# rf.net
KiCad netlist of a schematic drawn in Altium Designer
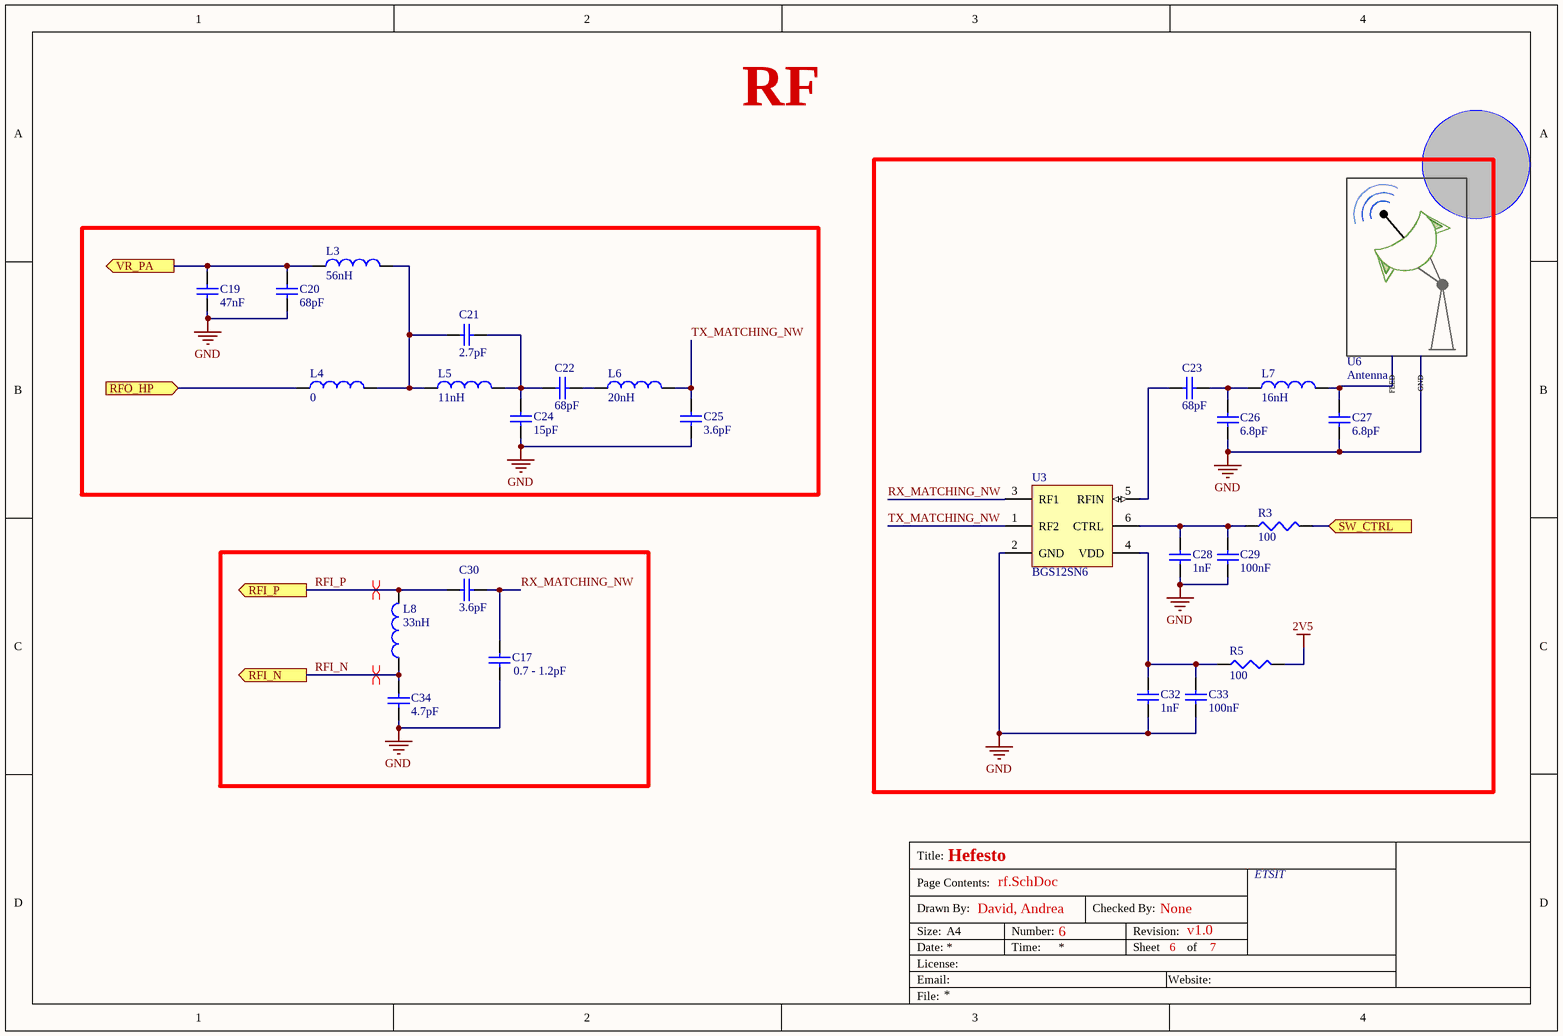
[diagram p0: rf.SchDoc]

(export (version "E")
  (design (tool "Eeschema 10.0.6"))
  (components
    (comp (ref "C17")
      (value "0.7 - 1.2pF")
      (footprint "1608[0603]")
      (description "Capacitor (Semiconductor SIM Model)")
      (fields (field (name "Comment") "Cap Semi") (field (name "PUBLISHER") "Altium Limited"))
      (libsource (lib "Miscellaneous Devices") (part "Cap Semi"))
    )
    (comp (ref "C19")
      (value "47nF")
      (footprint "1608[0603]")
      (description "Capacitor (Semiconductor SIM Model)")
      (fields (field (name "Comment") "Cap Semi") (field (name "PUBLISHER") "Altium Limited"))
      (libsource (lib "Miscellaneous Devices") (part "Cap Semi"))
    )
    (comp (ref "C20")
      (value "68pF")
      (footprint "1608[0603]")
      (description "Capacitor (Semiconductor SIM Model)")
      (fields (field (name "Comment") "Cap Semi") (field (name "PUBLISHER") "Altium Limited"))
      (libsource (lib "Miscellaneous Devices") (part "Cap Semi"))
    )
    (comp (ref "C21")
      (value "2.7pF")
      (footprint "1608[0603]")
      (description "Capacitor (Semiconductor SIM Model)")
      (fields (field (name "Comment") "Cap Semi") (field (name "PUBLISHER") "Altium Limited"))
      (libsource (lib "Miscellaneous Devices") (part "Cap Semi"))
    )
    (comp (ref "C22")
      (value "68pF")
      (footprint "1608[0603]")
      (description "Capacitor (Semiconductor SIM Model)")
      (fields (field (name "Comment") "Cap Semi") (field (name "PUBLISHER") "Altium Limited"))
      (libsource (lib "Miscellaneous Devices") (part "Cap Semi"))
    )
    (comp (ref "C23")
      (value "68pF")
      (footprint "1608[0603]")
      (description "Capacitor (Semiconductor SIM Model)")
      (fields (field (name "Comment") "Cap Semi") (field (name "PUBLISHER") "Altium Limited"))
      (libsource (lib "Miscellaneous Devices") (part "Cap Semi"))
    )
    (comp (ref "C24")
      (value "15pF")
      (footprint "1608[0603]")
      (description "Capacitor (Semiconductor SIM Model)")
      (fields (field (name "Comment") "Cap Semi") (field (name "PUBLISHER") "Altium Limited"))
      (libsource (lib "Miscellaneous Devices") (part "Cap Semi"))
    )
    (comp (ref "C25")
      (value "3.6pF")
      (footprint "1608[0603]")
      (description "Capacitor (Semiconductor SIM Model)")
      (fields (field (name "Comment") "Cap Semi") (field (name "PUBLISHER") "Altium Limited"))
      (libsource (lib "Miscellaneous Devices") (part "Cap Semi"))
    )
    (comp (ref "C26")
      (value "6.8pF")
      (footprint "1608[0603]")
      (description "Capacitor (Semiconductor SIM Model)")
      (fields (field (name "Comment") "Cap Semi") (field (name "PUBLISHER") "Altium Limited"))
      (libsource (lib "Miscellaneous Devices") (part "Cap Semi"))
    )
    (comp (ref "C27")
      (value "6.8pF")
      (footprint "1608[0603]")
      (description "Capacitor (Semiconductor SIM Model)")
      (fields (field (name "Comment") "Cap Semi") (field (name "PUBLISHER") "Altium Limited"))
      (libsource (lib "Miscellaneous Devices") (part "Cap Semi"))
    )
    (comp (ref "C28")
      (value "1nF")
      (footprint "1608[0603]")
      (description "Capacitor (Semiconductor SIM Model)")
      (fields (field (name "Comment") "Cap Semi") (field (name "PUBLISHER") "Altium Limited"))
      (libsource (lib "Miscellaneous Devices") (part "Cap Semi"))
    )
    (comp (ref "C29")
      (value "100nF")
      (footprint "1608[0603]")
      (description "Capacitor (Semiconductor SIM Model)")
      (fields (field (name "Comment") "Cap Semi") (field (name "PUBLISHER") "Altium Limited"))
      (libsource (lib "Miscellaneous Devices") (part "Cap Semi"))
    )
    (comp (ref "C30")
      (value "3.6pF")
      (footprint "1608[0603]")
      (description "Capacitor (Semiconductor SIM Model)")
      (fields (field (name "Comment") "Cap Semi") (field (name "PUBLISHER") "Altium Limited"))
      (libsource (lib "Miscellaneous Devices") (part "Cap Semi"))
    )
    (comp (ref "C32")
      (value "1nF")
      (footprint "1608[0603]")
      (description "Capacitor (Semiconductor SIM Model)")
      (fields (field (name "Comment") "Cap Semi") (field (name "PUBLISHER") "Altium Limited"))
      (libsource (lib "Miscellaneous Devices") (part "Cap Semi"))
    )
    (comp (ref "C33")
      (value "100nF")
      (footprint "1608[0603]")
      (description "Capacitor (Semiconductor SIM Model)")
      (fields (field (name "Comment") "Cap Semi") (field (name "PUBLISHER") "Altium Limited"))
      (libsource (lib "Miscellaneous Devices") (part "Cap Semi"))
    )
    (comp (ref "C34")
      (value "4.7pF")
      (footprint "1608[0603]")
      (description "Capacitor (Semiconductor SIM Model)")
      (fields (field (name "Comment") "Cap Semi") (field (name "PUBLISHER") "Altium Limited"))
      (libsource (lib "Miscellaneous Devices") (part "Cap Semi"))
    )
    (comp (ref "L3")
      (value "56nH")
      (footprint "0603")
      (description "Inductor")
      (fields (field (name "PUBLISHER") "Altium Limited"))
      (libsource (lib "Miscellaneous Devices") (part "Inductor"))
    )
    (comp (ref "L4")
      (value "0")
      (footprint "0603")
      (description "Inductor")
      (fields (field (name "PUBLISHER") "Altium Limited"))
      (libsource (lib "Miscellaneous Devices") (part "Inductor"))
    )
    (comp (ref "L5")
      (value "11nH")
      (footprint "0603")
      (description "Inductor")
      (fields (field (name "PUBLISHER") "Altium Limited"))
      (libsource (lib "Miscellaneous Devices") (part "Inductor"))
    )
    (comp (ref "L6")
      (value "20nH")
      (footprint "0603")
      (description "Inductor")
      (fields (field (name "PUBLISHER") "Altium Limited"))
      (libsource (lib "Miscellaneous Devices") (part "Inductor"))
    )
    (comp (ref "L7")
      (value "16nH")
      (footprint "0603")
      (description "Inductor")
      (fields (field (name "PUBLISHER") "Altium Limited"))
      (libsource (lib "Miscellaneous Devices") (part "Inductor"))
    )
    (comp (ref "L8")
      (value "33nH")
      (footprint "0603")
      (description "Inductor")
      (fields (field (name "PUBLISHER") "Altium Limited"))
      (libsource (lib "Miscellaneous Devices") (part "Inductor"))
    )
    (comp (ref "R3")
      (value "100")
      (footprint "J1-0603")
      (description "Resistor")
      (fields (field (name "Comment") "Res3") (field (name "PUBLISHER") "Altium Limited"))
      (libsource (lib "Miscellaneous Devices") (part "Res3"))
    )
    (comp (ref "R5")
      (value "100")
      (footprint "J1-0603")
      (description "Resistor")
      (fields (field (name "Comment") "Res3") (field (name "PUBLISHER") "Altium Limited"))
      (libsource (lib "Miscellaneous Devices") (part "Res3"))
    )
    (comp (ref "U3")
      (value "BGS12SN6")
      (footprint "INF-TSNP-6-2_V")
      (description "Wideband RF SPDT Switch, 0.1 to 6 GHz, TSNP-6, Reel, Green")
      (fields (field (name "MANUFACTURER") "Infineon"))
      (libsource (lib "Altium Content Vault") (part "INF-BGS12PL_SL6-TSLP-6-4-6"))
    )
    (comp (ref "U6")
      (value "Antenna")
      (footprint "Antenna_SWRA228")
      (libsource (lib "DEOP2023") (part "Antenna"))
    )
  )
  (nets
    (net (code "1") (name "/RFI_N") (class "Default")
      (node (ref "C34") (pin "2") (pinfunction "2_2") (pintype "passive"))
      (node (ref "L8") (pin "1") (pinfunction "1_1") (pintype "passive"))
    )
    (net (code "2") (name "/RFI_P") (class "Default")
      (node (ref "C30") (pin "2") (pinfunction "2_2") (pintype "passive"))
      (node (ref "L8") (pin "2") (pinfunction "2_2") (pintype "passive"))
    )
    (net (code "3") (name "/RFO_HP") (class "Default")
      (node (ref "L4") (pin "1") (pinfunction "1_1") (pintype "passive"))
    )
    (net (code "4") (name "/RX_MATCHING_NW") (class "Default")
      (node (ref "C17") (pin "2") (pinfunction "2_2") (pintype "passive"))
      (node (ref "C30") (pin "1") (pinfunction "1_1") (pintype "passive"))
      (node (ref "U3") (pin "3") (pinfunction "RF1_3") (pintype "passive"))
    )
    (net (code "5") (name "/SW_CTRL") (class "Default")
      (node (ref "R3") (pin "2") (pinfunction "2_2") (pintype "passive"))
    )
    (net (code "6") (name "/TX_MATCHING_NW") (class "Default")
      (node (ref "C25") (pin "2") (pinfunction "2_2") (pintype "passive"))
      (node (ref "L6") (pin "2") (pinfunction "2_2") (pintype "passive"))
      (node (ref "U3") (pin "1") (pinfunction "RF2_1") (pintype "passive"))
    )
    (net (code "7") (name "/VR_PA") (class "Default")
      (node (ref "C19") (pin "2") (pinfunction "2_2") (pintype "passive"))
      (node (ref "C20") (pin "2") (pinfunction "2_2") (pintype "passive"))
      (node (ref "L3") (pin "1") (pinfunction "1_1") (pintype "passive"))
    )
    (net (code "8") (name "2V5") (class "Default")
      (node (ref "R5") (pin "2") (pinfunction "2_2") (pintype "passive"))
    )
    (net (code "9") (name "GND") (class "Default")
      (node (ref "C17") (pin "1") (pinfunction "1_1") (pintype "passive"))
      (node (ref "C19") (pin "1") (pinfunction "1_1") (pintype "passive"))
      (node (ref "C20") (pin "1") (pinfunction "1_1") (pintype "passive"))
      (node (ref "C24") (pin "1") (pinfunction "1_1") (pintype "passive"))
      (node (ref "C25") (pin "1") (pinfunction "1_1") (pintype "passive"))
      (node (ref "C26") (pin "2") (pinfunction "2_2") (pintype "passive"))
      (node (ref "C27") (pin "2") (pinfunction "2_2") (pintype "passive"))
      (node (ref "C28") (pin "2") (pinfunction "2_2") (pintype "passive"))
      (node (ref "C29") (pin "2") (pinfunction "2_2") (pintype "passive"))
      (node (ref "C32") (pin "2") (pinfunction "2_2") (pintype "passive"))
      (node (ref "C33") (pin "2") (pinfunction "2_2") (pintype "passive"))
      (node (ref "C34") (pin "1") (pinfunction "1_1") (pintype "passive"))
      (node (ref "U3") (pin "2") (pinfunction "GND_2") (pintype "power_in"))
      (node (ref "U6") (pin "0") (pinfunction "GND_0") (pintype "power_in"))
    )
    (net (code "10") (name "Net-(C21-Pad1)") (class "Default")
      (node (ref "C21") (pin "1") (pinfunction "1_1") (pintype "passive"))
      (node (ref "C22") (pin "2") (pinfunction "2_2") (pintype "passive"))
      (node (ref "C24") (pin "2") (pinfunction "2_2") (pintype "passive"))
      (node (ref "L5") (pin "2") (pinfunction "2_2") (pintype "passive"))
    )
    (net (code "11") (name "Net-(C21-Pad2)") (class "Default")
      (node (ref "C21") (pin "2") (pinfunction "2_2") (pintype "passive"))
      (node (ref "L3") (pin "2") (pinfunction "2_2") (pintype "passive"))
      (node (ref "L4") (pin "2") (pinfunction "2_2") (pintype "passive"))
      (node (ref "L5") (pin "1") (pinfunction "1_1") (pintype "passive"))
    )
    (net (code "12") (name "Net-(C22-Pad1)") (class "Default")
      (node (ref "C22") (pin "1") (pinfunction "1_1") (pintype "passive"))
      (node (ref "L6") (pin "1") (pinfunction "1_1") (pintype "passive"))
    )
    (net (code "13") (name "Net-(C23-Pad1)") (class "Default")
      (node (ref "C23") (pin "1") (pinfunction "1_1") (pintype "passive"))
      (node (ref "C26") (pin "1") (pinfunction "1_1") (pintype "passive"))
      (node (ref "L7") (pin "1") (pinfunction "1_1") (pintype "passive"))
    )
    (net (code "14") (name "Net-(U3-CTRL)") (class "Default")
      (node (ref "C28") (pin "1") (pinfunction "1_1") (pintype "passive"))
      (node (ref "C29") (pin "1") (pinfunction "1_1") (pintype "passive"))
      (node (ref "R3") (pin "1") (pinfunction "1_1") (pintype "passive"))
      (node (ref "U3") (pin "6") (pinfunction "CTRL_6") (pintype "passive"))
    )
    (net (code "15") (name "Net-(U3-RFIN)") (class "Default")
      (node (ref "C23") (pin "2") (pinfunction "2_2") (pintype "passive"))
      (node (ref "U3") (pin "5") (pinfunction "RFIN_5") (pintype "bidirectional"))
    )
    (net (code "16") (name "Net-(U3-VDD)") (class "Default")
      (node (ref "C32") (pin "1") (pinfunction "1_1") (pintype "passive"))
      (node (ref "C33") (pin "1") (pinfunction "1_1") (pintype "passive"))
      (node (ref "R5") (pin "1") (pinfunction "1_1") (pintype "passive"))
      (node (ref "U3") (pin "4") (pinfunction "VDD_4") (pintype "power_in"))
    )
    (net (code "17") (name "Net-(U6-FEED)") (class "Default")
      (node (ref "C27") (pin "1") (pinfunction "1_1") (pintype "passive"))
      (node (ref "L7") (pin "2") (pinfunction "2_2") (pintype "passive"))
      (node (ref "U6") (pin "1") (pinfunction "FEED_1") (pintype "passive"))
    )
  )
)
